# HEA.net
KiCad netlist of a schematic drawn in EAGLE
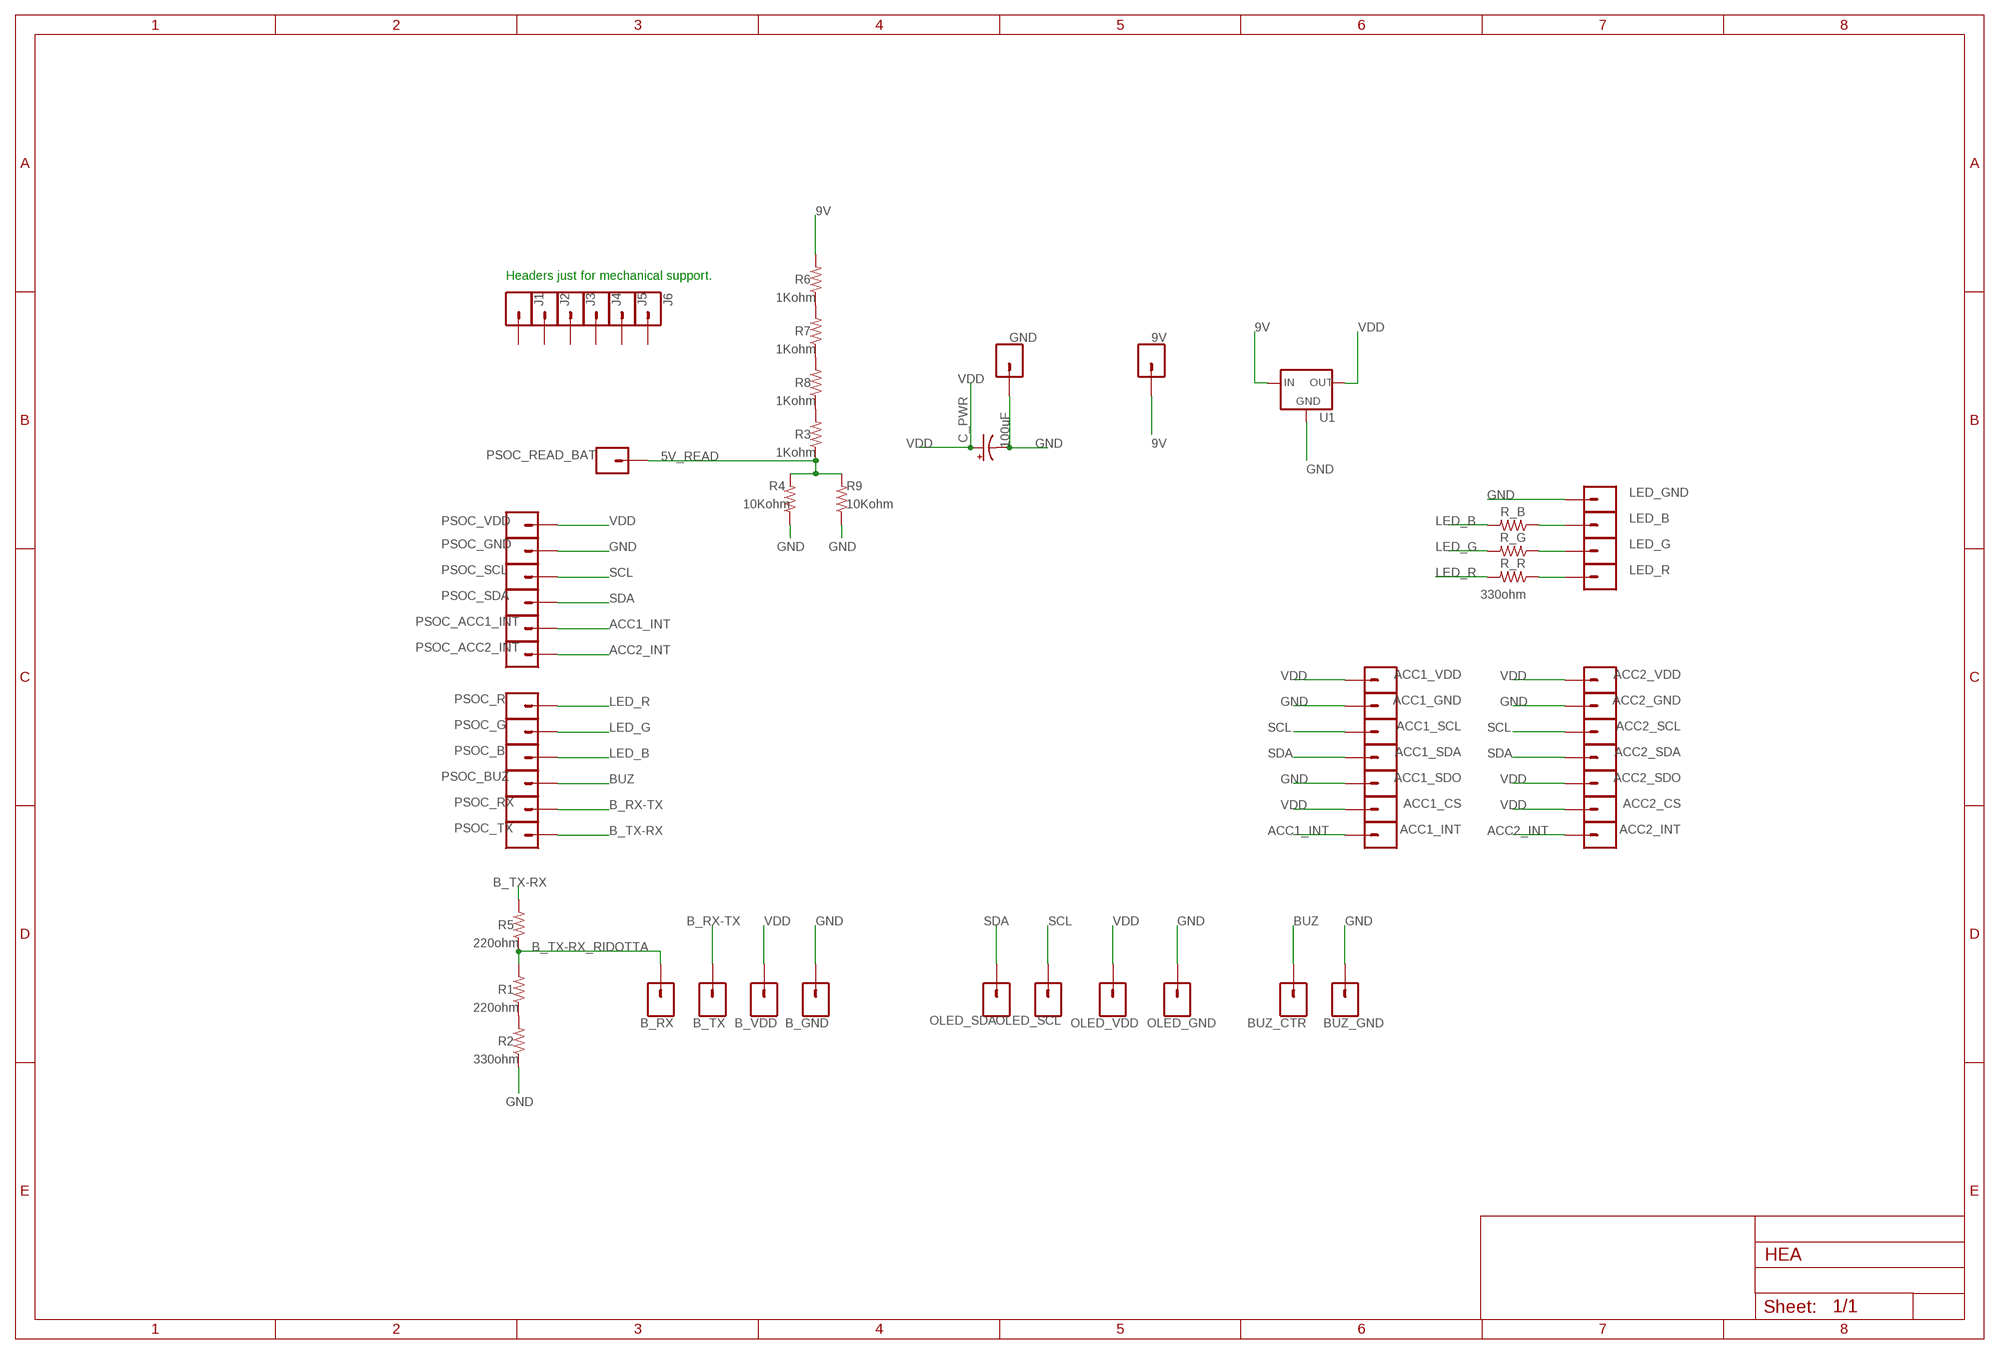
[diagram p0: schematic, sheet 1]

(export (version "E")
  (design (tool "Eeschema 10.0.6"))
  (components
    (comp (ref "9V")
      (value "CONN_01")
      (footprint "eagle-import:1X01")
      (libsource (lib "eagle-import") (part "CONN_01"))
    )
    (comp (ref "ACC1_CS")
      (value "CONN_01")
      (footprint "eagle-import:1X01")
      (libsource (lib "eagle-import") (part "CONN_01"))
    )
    (comp (ref "ACC1_GND")
      (value "CONN_01")
      (footprint "eagle-import:1X01")
      (libsource (lib "eagle-import") (part "CONN_01"))
    )
    (comp (ref "ACC1_INT")
      (value "CONN_01")
      (footprint "eagle-import:1X01")
      (libsource (lib "eagle-import") (part "CONN_01"))
    )
    (comp (ref "ACC1_SCL")
      (value "CONN_01")
      (footprint "eagle-import:1X01")
      (libsource (lib "eagle-import") (part "CONN_01"))
    )
    (comp (ref "ACC1_SDA")
      (value "CONN_01")
      (footprint "eagle-import:1X01")
      (libsource (lib "eagle-import") (part "CONN_01"))
    )
    (comp (ref "ACC1_SDO")
      (value "CONN_01")
      (footprint "eagle-import:1X01")
      (libsource (lib "eagle-import") (part "CONN_01"))
    )
    (comp (ref "ACC1_VDD")
      (value "CONN_01")
      (footprint "eagle-import:1X01")
      (libsource (lib "eagle-import") (part "CONN_01"))
    )
    (comp (ref "ACC2_CS")
      (value "CONN_01")
      (footprint "eagle-import:1X01")
      (libsource (lib "eagle-import") (part "CONN_01"))
    )
    (comp (ref "ACC2_GND")
      (value "CONN_01")
      (footprint "eagle-import:1X01")
      (libsource (lib "eagle-import") (part "CONN_01"))
    )
    (comp (ref "ACC2_INT")
      (value "CONN_01")
      (footprint "eagle-import:1X01")
      (libsource (lib "eagle-import") (part "CONN_01"))
    )
    (comp (ref "ACC2_SCL")
      (value "CONN_01")
      (footprint "eagle-import:1X01")
      (libsource (lib "eagle-import") (part "CONN_01"))
    )
    (comp (ref "ACC2_SDA")
      (value "CONN_01")
      (footprint "eagle-import:1X01")
      (libsource (lib "eagle-import") (part "CONN_01"))
    )
    (comp (ref "ACC2_SDO")
      (value "CONN_01")
      (footprint "eagle-import:1X01")
      (libsource (lib "eagle-import") (part "CONN_01"))
    )
    (comp (ref "ACC2_VDD")
      (value "CONN_01")
      (footprint "eagle-import:1X01")
      (libsource (lib "eagle-import") (part "CONN_01"))
    )
    (comp (ref "BUZ_CTR")
      (value "CONN_01")
      (footprint "eagle-import:1X01")
      (libsource (lib "eagle-import") (part "CONN_01"))
    )
    (comp (ref "BUZ_GND")
      (value "CONN_01")
      (footprint "eagle-import:1X01")
      (libsource (lib "eagle-import") (part "CONN_01"))
    )
    (comp (ref "B_GND")
      (value "CONN_01")
      (footprint "eagle-import:1X01")
      (libsource (lib "eagle-import") (part "CONN_01"))
    )
    (comp (ref "B_RX")
      (value "CONN_01")
      (footprint "eagle-import:1X01")
      (libsource (lib "eagle-import") (part "CONN_01"))
    )
    (comp (ref "B_TX")
      (value "CONN_01")
      (footprint "eagle-import:1X01")
      (libsource (lib "eagle-import") (part "CONN_01"))
    )
    (comp (ref "B_VDD")
      (value "CONN_01")
      (footprint "eagle-import:1X01")
      (libsource (lib "eagle-import") (part "CONN_01"))
    )
    (comp (ref "C_PWR")
      (value "10uF")
      (footprint "eagle-import:CPOL-RADIAL-2.5MM-5MM")
      (fields (field (name "CAPACITANCE") "100uF"))
      (libsource (lib "eagle-import") (part "10UF-POLAR-RADIAL-2.5MM-25V-20%"))
    )
    (comp (ref "GND")
      (value "CONN_01")
      (footprint "eagle-import:1X01")
      (libsource (lib "eagle-import") (part "CONN_01"))
    )
    (comp (ref "J1")
      (value "CONN_01")
      (footprint "eagle-import:1X01")
      (libsource (lib "eagle-import") (part "CONN_01"))
    )
    (comp (ref "J2")
      (value "CONN_01")
      (footprint "eagle-import:1X01")
      (libsource (lib "eagle-import") (part "CONN_01"))
    )
    (comp (ref "J3")
      (value "CONN_01")
      (footprint "eagle-import:1X01")
      (libsource (lib "eagle-import") (part "CONN_01"))
    )
    (comp (ref "J4")
      (value "CONN_01")
      (footprint "eagle-import:1X01")
      (libsource (lib "eagle-import") (part "CONN_01"))
    )
    (comp (ref "J5")
      (value "CONN_01")
      (footprint "eagle-import:1X01")
      (libsource (lib "eagle-import") (part "CONN_01"))
    )
    (comp (ref "J6")
      (value "CONN_01")
      (footprint "eagle-import:1X01")
      (libsource (lib "eagle-import") (part "CONN_01"))
    )
    (comp (ref "LED_B")
      (value "CONN_01")
      (footprint "eagle-import:1X01")
      (libsource (lib "eagle-import") (part "CONN_01"))
    )
    (comp (ref "LED_G")
      (value "CONN_01")
      (footprint "eagle-import:1X01")
      (libsource (lib "eagle-import") (part "CONN_01"))
    )
    (comp (ref "LED_GND")
      (value "CONN_01")
      (footprint "eagle-import:1X01")
      (libsource (lib "eagle-import") (part "CONN_01"))
    )
    (comp (ref "LED_R")
      (value "CONN_01")
      (footprint "eagle-import:1X01")
      (libsource (lib "eagle-import") (part "CONN_01"))
    )
    (comp (ref "OLED_GND")
      (value "CONN_01")
      (footprint "eagle-import:1X01")
      (libsource (lib "eagle-import") (part "CONN_01"))
    )
    (comp (ref "OLED_SCL")
      (value "CONN_01")
      (footprint "eagle-import:1X01")
      (libsource (lib "eagle-import") (part "CONN_01"))
    )
    (comp (ref "OLED_SDA")
      (value "CONN_01")
      (footprint "eagle-import:1X01")
      (libsource (lib "eagle-import") (part "CONN_01"))
    )
    (comp (ref "OLED_VDD")
      (value "CONN_01")
      (footprint "eagle-import:1X01")
      (libsource (lib "eagle-import") (part "CONN_01"))
    )
    (comp (ref "PSOC_ACC1_INT")
      (value "CONN_01")
      (footprint "eagle-import:1X01")
      (libsource (lib "eagle-import") (part "CONN_01"))
    )
    (comp (ref "PSOC_ACC2_INT")
      (value "CONN_01")
      (footprint "eagle-import:1X01")
      (libsource (lib "eagle-import") (part "CONN_01"))
    )
    (comp (ref "PSOC_B")
      (value "CONN_01")
      (footprint "eagle-import:1X01")
      (libsource (lib "eagle-import") (part "CONN_01"))
    )
    (comp (ref "PSOC_BUZ")
      (value "CONN_01")
      (footprint "eagle-import:1X01")
      (libsource (lib "eagle-import") (part "CONN_01"))
    )
    (comp (ref "PSOC_G")
      (value "CONN_01")
      (footprint "eagle-import:1X01")
      (libsource (lib "eagle-import") (part "CONN_01"))
    )
    (comp (ref "PSOC_GND")
      (value "CONN_01")
      (footprint "eagle-import:1X01")
      (libsource (lib "eagle-import") (part "CONN_01"))
    )
    (comp (ref "PSOC_R")
      (value "CONN_01")
      (footprint "eagle-import:1X01")
      (libsource (lib "eagle-import") (part "CONN_01"))
    )
    (comp (ref "PSOC_READ_BAT")
      (value "CONN_01")
      (footprint "eagle-import:1X01")
      (libsource (lib "eagle-import") (part "CONN_01"))
    )
    (comp (ref "PSOC_RX")
      (value "CONN_01")
      (footprint "eagle-import:1X01")
      (libsource (lib "eagle-import") (part "CONN_01"))
    )
    (comp (ref "PSOC_SCL")
      (value "CONN_01")
      (footprint "eagle-import:1X01")
      (libsource (lib "eagle-import") (part "CONN_01"))
    )
    (comp (ref "PSOC_SDA")
      (value "CONN_01")
      (footprint "eagle-import:1X01")
      (libsource (lib "eagle-import") (part "CONN_01"))
    )
    (comp (ref "PSOC_TX")
      (value "CONN_01")
      (footprint "eagle-import:1X01")
      (libsource (lib "eagle-import") (part "CONN_01"))
    )
    (comp (ref "PSOC_VDD")
      (value "CONN_01")
      (footprint "eagle-import:1X01")
      (libsource (lib "eagle-import") (part "CONN_01"))
    )
    (comp (ref "R1")
      (value "RESISTORAXIAL-0.3")
      (footprint "eagle-import:AXIAL-0.3")
      (fields (field (name "RESISTANCE") "220ohm"))
      (libsource (lib "eagle-import") (part "RESISTORAXIAL-0.3"))
    )
    (comp (ref "R2")
      (value "RESISTORAXIAL-0.3")
      (footprint "eagle-import:AXIAL-0.3")
      (fields (field (name "RESISTANCE") "330ohm"))
      (libsource (lib "eagle-import") (part "RESISTORAXIAL-0.3"))
    )
    (comp (ref "R3")
      (value "RESISTORAXIAL-0.3")
      (footprint "eagle-import:AXIAL-0.3")
      (fields (field (name "RESISTANCE") "1Kohm"))
      (libsource (lib "eagle-import") (part "RESISTORAXIAL-0.3"))
    )
    (comp (ref "R4")
      (value "RESISTORAXIAL-0.3")
      (footprint "eagle-import:AXIAL-0.3")
      (fields (field (name "RESISTANCE") "10Kohm"))
      (libsource (lib "eagle-import") (part "RESISTORAXIAL-0.3"))
    )
    (comp (ref "R5")
      (value "RESISTORAXIAL-0.3")
      (footprint "eagle-import:AXIAL-0.3")
      (fields (field (name "RESISTANCE") "220ohm"))
      (libsource (lib "eagle-import") (part "RESISTORAXIAL-0.3"))
    )
    (comp (ref "R6")
      (value "RESISTORAXIAL-0.3")
      (footprint "eagle-import:AXIAL-0.3")
      (fields (field (name "RESISTANCE") "1Kohm"))
      (libsource (lib "eagle-import") (part "RESISTORAXIAL-0.3"))
    )
    (comp (ref "R7")
      (value "RESISTORAXIAL-0.3")
      (footprint "eagle-import:AXIAL-0.3")
      (fields (field (name "RESISTANCE") "1Kohm"))
      (libsource (lib "eagle-import") (part "RESISTORAXIAL-0.3"))
    )
    (comp (ref "R8")
      (value "RESISTORAXIAL-0.3")
      (footprint "eagle-import:AXIAL-0.3")
      (fields (field (name "RESISTANCE") "1Kohm"))
      (libsource (lib "eagle-import") (part "RESISTORAXIAL-0.3"))
    )
    (comp (ref "R9")
      (value "RESISTORAXIAL-0.3")
      (footprint "eagle-import:AXIAL-0.3")
      (fields (field (name "RESISTANCE") "10Kohm"))
      (libsource (lib "eagle-import") (part "RESISTORAXIAL-0.3"))
    )
    (comp (ref "R_B")
      (value "RESISTORAXIAL-0.3")
      (footprint "eagle-import:AXIAL-0.3")
      (libsource (lib "eagle-import") (part "RESISTORAXIAL-0.3"))
    )
    (comp (ref "R_G")
      (value "RESISTORAXIAL-0.3")
      (footprint "eagle-import:AXIAL-0.3")
      (libsource (lib "eagle-import") (part "RESISTORAXIAL-0.3"))
    )
    (comp (ref "R_R")
      (value "RESISTORAXIAL-0.3")
      (footprint "eagle-import:AXIAL-0.3")
      (fields (field (name "RESTISTANCE") "330ohm"))
      (libsource (lib "eagle-import") (part "RESISTORAXIAL-0.3"))
    )
    (comp (ref "U1")
      (value "V_REG_78XX-TO-220")
      (footprint "eagle-import:TO-220-ALT")
      (libsource (lib "eagle-import") (part "V_REG_78XX-TO-220"))
    )
  )
  (nets
    (net (code "1") (name "/5V_READ") (class "Default")
      (node (ref "PSOC_READ_BAT") (pin "1") (pinfunction "1_1") (pintype "passive"))
      (node (ref "R3") (pin "P$1") (pinfunction "1_P$1") (pintype "passive"))
      (node (ref "R4") (pin "P$2") (pinfunction "2_P$2") (pintype "passive"))
      (node (ref "R9") (pin "P$2") (pinfunction "2_P$2") (pintype "passive"))
    )
    (net (code "2") (name "/9V") (class "Default")
      (node (ref "9V") (pin "1") (pinfunction "1_1") (pintype "passive"))
      (node (ref "R6") (pin "P$2") (pinfunction "2_P$2") (pintype "passive"))
      (node (ref "U1") (pin "IN") (pinfunction "IN_IN") (pintype "input"))
    )
    (net (code "3") (name "/ACC1_INT") (class "Default")
      (node (ref "ACC1_INT") (pin "1") (pinfunction "1_1") (pintype "passive"))
      (node (ref "PSOC_ACC1_INT") (pin "1") (pinfunction "1_1") (pintype "passive"))
    )
    (net (code "4") (name "/ACC2_INT") (class "Default")
      (node (ref "ACC2_INT") (pin "1") (pinfunction "1_1") (pintype "passive"))
      (node (ref "PSOC_ACC2_INT") (pin "1") (pinfunction "1_1") (pintype "passive"))
    )
    (net (code "5") (name "/BUZ") (class "Default")
      (node (ref "BUZ_CTR") (pin "1") (pinfunction "1_1") (pintype "passive"))
      (node (ref "PSOC_BUZ") (pin "1") (pinfunction "1_1") (pintype "passive"))
    )
    (net (code "6") (name "/B_RX-TX") (class "Default")
      (node (ref "B_TX") (pin "1") (pinfunction "1_1") (pintype "passive"))
      (node (ref "PSOC_RX") (pin "1") (pinfunction "1_1") (pintype "passive"))
    )
    (net (code "7") (name "/B_TX-RX") (class "Default")
      (node (ref "PSOC_TX") (pin "1") (pinfunction "1_1") (pintype "passive"))
      (node (ref "R5") (pin "P$2") (pinfunction "2_P$2") (pintype "passive"))
    )
    (net (code "8") (name "/B_TX-RX_RIDOTTA") (class "Default")
      (node (ref "B_RX") (pin "1") (pinfunction "1_1") (pintype "passive"))
      (node (ref "R1") (pin "P$2") (pinfunction "2_P$2") (pintype "passive"))
      (node (ref "R5") (pin "P$1") (pinfunction "1_P$1") (pintype "passive"))
    )
    (net (code "9") (name "/GND") (class "Default")
      (node (ref "ACC1_GND") (pin "1") (pinfunction "1_1") (pintype "passive"))
      (node (ref "ACC1_SDO") (pin "1") (pinfunction "1_1") (pintype "passive"))
      (node (ref "ACC2_GND") (pin "1") (pinfunction "1_1") (pintype "passive"))
      (node (ref "BUZ_GND") (pin "1") (pinfunction "1_1") (pintype "passive"))
      (node (ref "B_GND") (pin "1") (pinfunction "1_1") (pintype "passive"))
      (node (ref "C_PWR") (pin "2") (pinfunction "-_2") (pintype "passive"))
      (node (ref "GND") (pin "1") (pinfunction "1_1") (pintype "passive"))
      (node (ref "LED_GND") (pin "1") (pinfunction "1_1") (pintype "passive"))
      (node (ref "OLED_GND") (pin "1") (pinfunction "1_1") (pintype "passive"))
      (node (ref "PSOC_GND") (pin "1") (pinfunction "1_1") (pintype "passive"))
      (node (ref "R2") (pin "P$1") (pinfunction "1_P$1") (pintype "passive"))
      (node (ref "R4") (pin "P$1") (pinfunction "1_P$1") (pintype "passive"))
      (node (ref "R9") (pin "P$1") (pinfunction "1_P$1") (pintype "passive"))
      (node (ref "U1") (pin "GND") (pinfunction "GND_GND") (pintype "input"))
    )
    (net (code "10") (name "/LED_B") (class "Default")
      (node (ref "PSOC_B") (pin "1") (pinfunction "1_1") (pintype "passive"))
      (node (ref "R_B") (pin "P$2") (pinfunction "2_P$2") (pintype "passive"))
    )
    (net (code "11") (name "/LED_G") (class "Default")
      (node (ref "PSOC_G") (pin "1") (pinfunction "1_1") (pintype "passive"))
      (node (ref "R_G") (pin "P$2") (pinfunction "2_P$2") (pintype "passive"))
    )
    (net (code "12") (name "/LED_R") (class "Default")
      (node (ref "PSOC_R") (pin "1") (pinfunction "1_1") (pintype "passive"))
      (node (ref "R_R") (pin "P$2") (pinfunction "2_P$2") (pintype "passive"))
    )
    (net (code "13") (name "/SCL") (class "Default")
      (node (ref "ACC1_SCL") (pin "1") (pinfunction "1_1") (pintype "passive"))
      (node (ref "ACC2_SCL") (pin "1") (pinfunction "1_1") (pintype "passive"))
      (node (ref "OLED_SCL") (pin "1") (pinfunction "1_1") (pintype "passive"))
      (node (ref "PSOC_SCL") (pin "1") (pinfunction "1_1") (pintype "passive"))
    )
    (net (code "14") (name "/SDA") (class "Default")
      (node (ref "ACC1_SDA") (pin "1") (pinfunction "1_1") (pintype "passive"))
      (node (ref "ACC2_SDA") (pin "1") (pinfunction "1_1") (pintype "passive"))
      (node (ref "OLED_SDA") (pin "1") (pinfunction "1_1") (pintype "passive"))
      (node (ref "PSOC_SDA") (pin "1") (pinfunction "1_1") (pintype "passive"))
    )
    (net (code "15") (name "/VDD") (class "Default")
      (node (ref "ACC1_CS") (pin "1") (pinfunction "1_1") (pintype "passive"))
      (node (ref "ACC1_VDD") (pin "1") (pinfunction "1_1") (pintype "passive"))
      (node (ref "ACC2_CS") (pin "1") (pinfunction "1_1") (pintype "passive"))
      (node (ref "ACC2_SDO") (pin "1") (pinfunction "1_1") (pintype "passive"))
      (node (ref "ACC2_VDD") (pin "1") (pinfunction "1_1") (pintype "passive"))
      (node (ref "B_VDD") (pin "1") (pinfunction "1_1") (pintype "passive"))
      (node (ref "C_PWR") (pin "1") (pinfunction "+_1") (pintype "passive"))
      (node (ref "OLED_VDD") (pin "1") (pinfunction "1_1") (pintype "passive"))
      (node (ref "PSOC_VDD") (pin "1") (pinfunction "1_1") (pintype "passive"))
      (node (ref "U1") (pin "OUT") (pinfunction "OUT_OUT") (pintype "passive"))
    )
    (net (code "16") (name "Net-(R1-1)") (class "Default")
      (node (ref "R1") (pin "P$1") (pinfunction "1_P$1") (pintype "passive"))
      (node (ref "R2") (pin "P$2") (pinfunction "2_P$2") (pintype "passive"))
    )
    (net (code "17") (name "Net-(R3-2)") (class "Default")
      (node (ref "R3") (pin "P$2") (pinfunction "2_P$2") (pintype "passive"))
      (node (ref "R8") (pin "P$1") (pinfunction "1_P$1") (pintype "passive"))
    )
    (net (code "18") (name "Net-(R6-1)") (class "Default")
      (node (ref "R6") (pin "P$1") (pinfunction "1_P$1") (pintype "passive"))
      (node (ref "R7") (pin "P$2") (pinfunction "2_P$2") (pintype "passive"))
    )
    (net (code "19") (name "Net-(R7-1)") (class "Default")
      (node (ref "R7") (pin "P$1") (pinfunction "1_P$1") (pintype "passive"))
      (node (ref "R8") (pin "P$2") (pinfunction "2_P$2") (pintype "passive"))
    )
    (net (code "20") (name "Net-(R_B-1)") (class "Default")
      (node (ref "LED_B") (pin "1") (pinfunction "1_1") (pintype "passive"))
      (node (ref "R_B") (pin "P$1") (pinfunction "1_P$1") (pintype "passive"))
    )
    (net (code "21") (name "Net-(R_G-1)") (class "Default")
      (node (ref "LED_G") (pin "1") (pinfunction "1_1") (pintype "passive"))
      (node (ref "R_G") (pin "P$1") (pinfunction "1_P$1") (pintype "passive"))
    )
    (net (code "22") (name "Net-(R_R-1)") (class "Default")
      (node (ref "LED_R") (pin "1") (pinfunction "1_1") (pintype "passive"))
      (node (ref "R_R") (pin "P$1") (pinfunction "1_P$1") (pintype "passive"))
    )
    (net (code "23") (name "unconnected-(J1-Pad1)") (class "Default")
      (node (ref "J1") (pin "1") (pinfunction "1_1") (pintype "passive"))
    )
    (net (code "24") (name "unconnected-(J2-Pad1)") (class "Default")
      (node (ref "J2") (pin "1") (pinfunction "1_1") (pintype "passive"))
    )
    (net (code "25") (name "unconnected-(J3-Pad1)") (class "Default")
      (node (ref "J3") (pin "1") (pinfunction "1_1") (pintype "passive"))
    )
    (net (code "26") (name "unconnected-(J4-Pad1)") (class "Default")
      (node (ref "J4") (pin "1") (pinfunction "1_1") (pintype "passive"))
    )
    (net (code "27") (name "unconnected-(J5-Pad1)") (class "Default")
      (node (ref "J5") (pin "1") (pinfunction "1_1") (pintype "passive"))
    )
    (net (code "28") (name "unconnected-(J6-Pad1)") (class "Default")
      (node (ref "J6") (pin "1") (pinfunction "1_1") (pintype "passive"))
    )
  )
)
